# MDL_RECEPTOR_IRF.net
KiCad netlist of a schematic drawn in Altium Designer
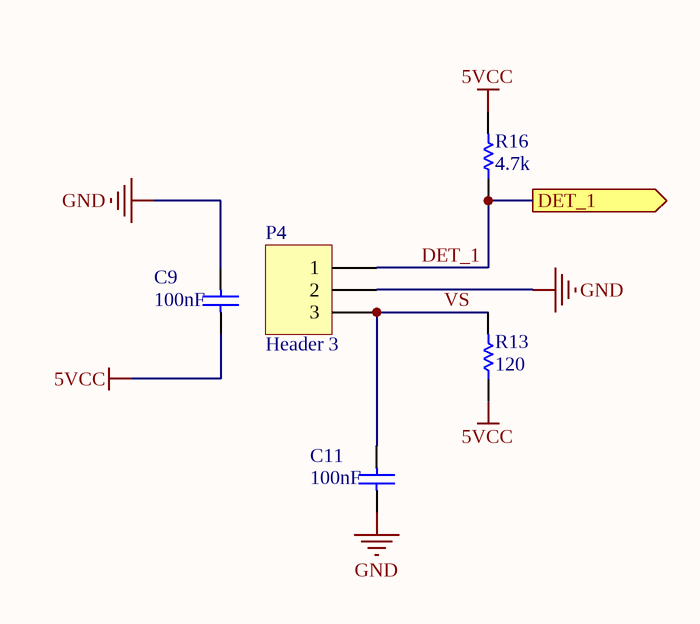
[diagram p0: MDL_RECEPTOR_IRF.SchDoc]

(export (version "E")
  (design (tool "Eeschema 10.0.6"))
  (components
    (comp (ref "C9")
      (value "100nF")
      (footprint "VP44-2.5")
      (description "Dipped Radial Multilayer Ceramic Capacitor X7R: 220nF, 100V")
      (fields (field (name "Comment") "VP44BY224JB") (field (name "PUBLISHER") "Altium Limited"))
      (libsource (lib "Vishay Vitramon Ceramic Dipped Capacitor") (part "VP44BY224JB"))
    )
    (comp (ref "C11")
      (value "100nF")
      (footprint "VP44-2.5")
      (description "Dipped Radial Multilayer Ceramic Capacitor X7R: 220nF, 100V")
      (fields (field (name "Comment") "VP44BY224JB") (field (name "PUBLISHER") "Altium Limited"))
      (libsource (lib "Vishay Vitramon Ceramic Dipped Capacitor") (part "VP44BY224JB"))
    )
    (comp (ref "P4")
      (value "Header 3")
      (footprint "HDR1X3")
      (description "Header, 3-Pin")
      (fields (field (name "PUBLISHER") "Altium Limited"))
      (libsource (lib "Miscellaneous Connectors") (part "Header 3"))
    )
    (comp (ref "R13")
      (value "120")
      (footprint "AXIAL-0.3")
      (description "Resistor")
      (fields (field (name "Comment") "Res") (field (name "PUBLISHER") "Altium Limited"))
      (libsource (lib "Miscellaneous Devices") (part "Res1"))
    )
    (comp (ref "R16")
      (value "4.7k")
      (footprint "AXIAL-0.3")
      (description "Resistor")
      (fields (field (name "Comment") "Res") (field (name "PUBLISHER") "Altium Limited"))
      (libsource (lib "Miscellaneous Devices") (part "Res1"))
    )
  )
  (nets
    (net (code "1") (name "/DET_1") (class "Default")
      (node (ref "P4") (pin "1") (pinfunction "1_1") (pintype "passive"))
      (node (ref "R16") (pin "1") (pinfunction "1_1") (pintype "passive"))
    )
    (net (code "2") (name "/VS") (class "Default")
      (node (ref "C11") (pin "1") (pinfunction "1_1") (pintype "passive"))
      (node (ref "P4") (pin "3") (pinfunction "3_3") (pintype "passive"))
      (node (ref "R13") (pin "2") (pinfunction "2_2") (pintype "passive"))
    )
    (net (code "3") (name "5VCC") (class "Default")
      (node (ref "C9") (pin "2") (pinfunction "2_2") (pintype "passive"))
      (node (ref "R13") (pin "1") (pinfunction "1_1") (pintype "passive"))
      (node (ref "R16") (pin "2") (pinfunction "2_2") (pintype "passive"))
    )
    (net (code "4") (name "GND") (class "Default")
      (node (ref "C11") (pin "2") (pinfunction "2_2") (pintype "passive"))
      (node (ref "C9") (pin "1") (pinfunction "1_1") (pintype "passive"))
      (node (ref "P4") (pin "2") (pinfunction "2_2") (pintype "passive"))
    )
  )
)
